# BLE_--_HM-10_--_Breakout_v0_9_4.net
KiCad netlist of a schematic drawn in EAGLE
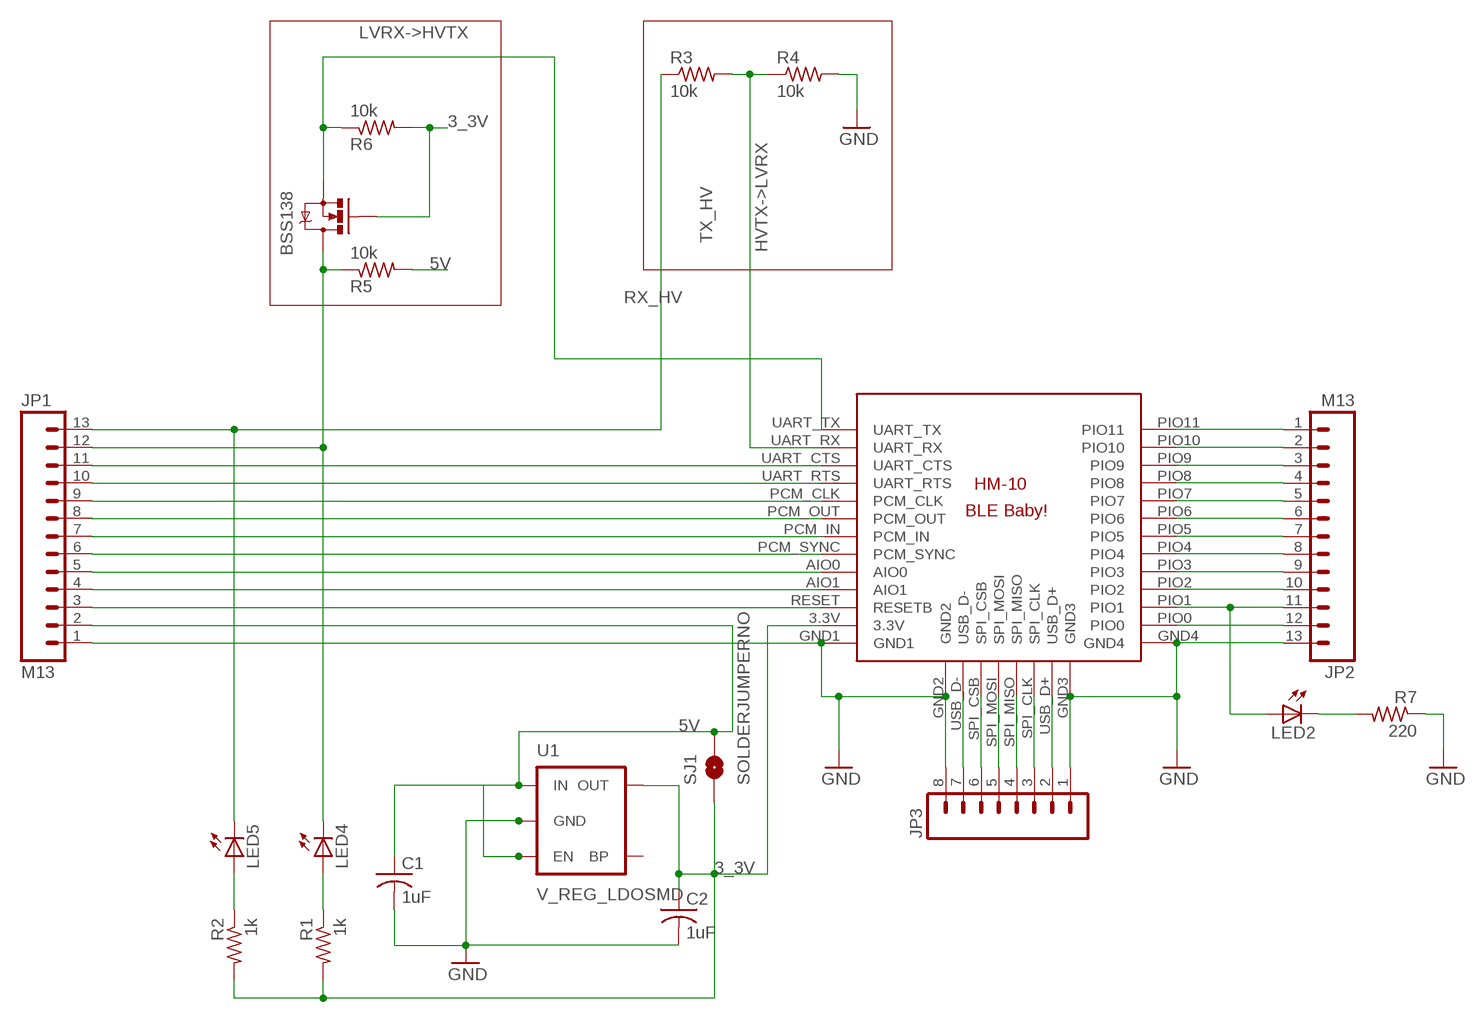
[diagram p0: schematic, sheet 1]

(export (version "E")
  (design (tool "Eeschema 10.0.6"))
  (components
    (comp (ref "BSS138")
      (value "MOSFET-NCHANNELSMD")
      (footprint "eagle-import:SOT23-3")
      (libsource (lib "eagle-import") (part "MOSFET-NCHANNELSMD"))
    )
    (comp (ref "C1")
      (value "1uF")
      (footprint "eagle-import:C0805K")
      (libsource (lib "eagle-import") (part "C-USC0805K"))
    )
    (comp (ref "C2")
      (value "1uF")
      (footprint "eagle-import:C0805K")
      (libsource (lib "eagle-import") (part "C-USC0805K"))
    )
    (comp (ref "JP1")
      (value "M13")
      (footprint "eagle-import:1X13")
      (libsource (lib "eagle-import") (part "M13"))
    )
    (comp (ref "JP2")
      (value "M13")
      (footprint "eagle-import:1X13")
      (libsource (lib "eagle-import") (part "M13"))
    )
    (comp (ref "JP3")
      (value "M081X08")
      (footprint "eagle-import:1X08")
      (libsource (lib "eagle-import") (part "M081X08"))
    )
    (comp (ref "LED2")
      (value "LED0603")
      (footprint "eagle-import:LED-0603")
      (libsource (lib "eagle-import") (part "LED0603"))
    )
    (comp (ref "LED4")
      (value "LED0603")
      (footprint "eagle-import:LED-0603")
      (libsource (lib "eagle-import") (part "LED0603"))
    )
    (comp (ref "LED5")
      (value "LED0603")
      (footprint "eagle-import:LED-0603")
      (libsource (lib "eagle-import") (part "LED0603"))
    )
    (comp (ref "R1")
      (value "1k")
      (footprint "eagle-import:M0805")
      (libsource (lib "eagle-import") (part "R-US_M0805"))
    )
    (comp (ref "R2")
      (value "1k")
      (footprint "eagle-import:M0805")
      (libsource (lib "eagle-import") (part "R-US_M0805"))
    )
    (comp (ref "R3")
      (value "10k")
      (footprint "eagle-import:M0805")
      (libsource (lib "eagle-import") (part "R-US_M0805"))
    )
    (comp (ref "R4")
      (value "10k")
      (footprint "eagle-import:M0805")
      (libsource (lib "eagle-import") (part "R-US_M0805"))
    )
    (comp (ref "R5")
      (value "10k")
      (footprint "eagle-import:M0805")
      (libsource (lib "eagle-import") (part "R-US_M0805"))
    )
    (comp (ref "R6")
      (value "10k")
      (footprint "eagle-import:M0805")
      (libsource (lib "eagle-import") (part "R-US_M0805"))
    )
    (comp (ref "R7")
      (value "220")
      (footprint "eagle-import:M0805")
      (libsource (lib "eagle-import") (part "R-US_M0805"))
    )
    (comp (ref "SJ1")
      (value "SOLDERJUMPERNO")
      (footprint "eagle-import:SJ_2S-NO")
      (libsource (lib "eagle-import") (part "SOLDERJUMPERNO"))
    )
    (comp (ref "U$1")
      (value "BLE-HM-10")
      (footprint "eagle-import:BLE-HM-10")
      (libsource (lib "eagle-import") (part "BLE-HM-10"))
    )
    (comp (ref "U1")
      (value "V_REG_LDOSMD")
      (footprint "eagle-import:SOT23-5")
      (libsource (lib "eagle-import") (part "V_REG_LDOSMD"))
    )
  )
  (nets
    (net (code "1") (name "/3_3V") (class "Default")
      (node (ref "BSS138") (pin "1") (pinfunction "G_1") (pintype "passive"))
      (node (ref "C2") (pin "1") (pinfunction "1_1") (pintype "passive"))
      (node (ref "R1") (pin "2") (pinfunction "2_2") (pintype "passive"))
      (node (ref "R2") (pin "2") (pinfunction "2_2") (pintype "passive"))
      (node (ref "R6") (pin "2") (pinfunction "2_2") (pintype "passive"))
      (node (ref "SJ1") (pin "1") (pinfunction "1_1") (pintype "passive"))
      (node (ref "U$1") (pin "3.3V") (pinfunction "3.3V_3.3V") (pintype "bidirectional"))
      (node (ref "U1") (pin "5") (pinfunction "OUT_5") (pintype "passive"))
    )
    (net (code "2") (name "/5V") (class "Default")
      (node (ref "C1") (pin "1") (pinfunction "1_1") (pintype "passive"))
      (node (ref "JP1") (pin "2") (pinfunction "2_2") (pintype "passive"))
      (node (ref "R5") (pin "2") (pinfunction "2_2") (pintype "passive"))
      (node (ref "SJ1") (pin "2") (pinfunction "2_2") (pintype "passive"))
      (node (ref "U1") (pin "1") (pinfunction "IN_1") (pintype "input"))
      (node (ref "U1") (pin "3") (pinfunction "EN_3") (pintype "input"))
    )
    (net (code "3") (name "/HVTX->LVRX") (class "Default")
      (node (ref "R3") (pin "2") (pinfunction "2_2") (pintype "passive"))
      (node (ref "R4") (pin "1") (pinfunction "1_1") (pintype "passive"))
      (node (ref "U$1") (pin "UART_RX") (pinfunction "UART_RX_UART_RX") (pintype "bidirectional"))
    )
    (net (code "4") (name "/LVRX->HVTX") (class "Default")
      (node (ref "BSS138") (pin "2") (pinfunction "S_2") (pintype "passive"))
      (node (ref "R6") (pin "1") (pinfunction "1_1") (pintype "passive"))
      (node (ref "U$1") (pin "UART_TX") (pinfunction "UART_TX_UART_TX") (pintype "bidirectional"))
    )
    (net (code "5") (name "/RX_HV") (class "Default")
      (node (ref "BSS138") (pin "3") (pinfunction "D_3") (pintype "passive"))
      (node (ref "JP1") (pin "12") (pinfunction "12_12") (pintype "passive"))
      (node (ref "LED4") (pin "C") (pinfunction "C_C") (pintype "passive"))
      (node (ref "R5") (pin "1") (pinfunction "1_1") (pintype "passive"))
    )
    (net (code "6") (name "/TX_HV") (class "Default")
      (node (ref "JP1") (pin "13") (pinfunction "13_13") (pintype "passive"))
      (node (ref "LED5") (pin "C") (pinfunction "C_C") (pintype "passive"))
      (node (ref "R3") (pin "1") (pinfunction "1_1") (pintype "passive"))
    )
    (net (code "7") (name "GND") (class "Default")
      (node (ref "C1") (pin "2") (pinfunction "2_2") (pintype "passive"))
      (node (ref "C2") (pin "2") (pinfunction "2_2") (pintype "passive"))
      (node (ref "JP1") (pin "1") (pinfunction "1_1") (pintype "passive"))
      (node (ref "JP2") (pin "13") (pinfunction "13_13") (pintype "passive"))
      (node (ref "JP3") (pin "1") (pinfunction "1_1") (pintype "passive"))
      (node (ref "JP3") (pin "8") (pinfunction "8_8") (pintype "passive"))
      (node (ref "R4") (pin "2") (pinfunction "2_2") (pintype "passive"))
      (node (ref "R7") (pin "1") (pinfunction "1_1") (pintype "passive"))
      (node (ref "U$1") (pin "GND1") (pinfunction "GND1_GND1") (pintype "bidirectional"))
      (node (ref "U$1") (pin "GND2") (pinfunction "GND2_GND2") (pintype "bidirectional"))
      (node (ref "U$1") (pin "GND3") (pinfunction "GND3_GND3") (pintype "bidirectional"))
      (node (ref "U$1") (pin "GND4") (pinfunction "GND4_GND4") (pintype "bidirectional"))
      (node (ref "U1") (pin "2") (pinfunction "GND_2") (pintype "input"))
    )
    (net (code "8") (name "Net-(JP1-Pad4)") (class "Default")
      (node (ref "JP1") (pin "4") (pinfunction "4_4") (pintype "passive"))
      (node (ref "U$1") (pin "AIO1") (pinfunction "AIO1_AIO1") (pintype "bidirectional"))
    )
    (net (code "9") (name "Net-(JP1-Pad5)") (class "Default")
      (node (ref "JP1") (pin "5") (pinfunction "5_5") (pintype "passive"))
      (node (ref "U$1") (pin "AIO0") (pinfunction "AIO0_AIO0") (pintype "bidirectional"))
    )
    (net (code "10") (name "Net-(JP1-Pad6)") (class "Default")
      (node (ref "JP1") (pin "6") (pinfunction "6_6") (pintype "passive"))
      (node (ref "U$1") (pin "PCM_SYNC") (pinfunction "PCM_SYNC_PCM_SYNC") (pintype "bidirectional"))
    )
    (net (code "11") (name "Net-(JP1-Pad7)") (class "Default")
      (node (ref "JP1") (pin "7") (pinfunction "7_7") (pintype "passive"))
      (node (ref "U$1") (pin "PCM_IN") (pinfunction "PCM_IN_PCM_IN") (pintype "bidirectional"))
    )
    (net (code "12") (name "Net-(JP1-Pad8)") (class "Default")
      (node (ref "JP1") (pin "8") (pinfunction "8_8") (pintype "passive"))
      (node (ref "U$1") (pin "PCM_OUT") (pinfunction "PCM_OUT_PCM_OUT") (pintype "bidirectional"))
    )
    (net (code "13") (name "Net-(JP1-Pad9)") (class "Default")
      (node (ref "JP1") (pin "9") (pinfunction "9_9") (pintype "passive"))
      (node (ref "U$1") (pin "PCM_CLK") (pinfunction "PCM_CLK_PCM_CLK") (pintype "bidirectional"))
    )
    (net (code "14") (name "Net-(JP1-Pad10)") (class "Default")
      (node (ref "JP1") (pin "10") (pinfunction "10_10") (pintype "passive"))
      (node (ref "U$1") (pin "UART_RTS") (pinfunction "UART_RTS_UART_RTS") (pintype "bidirectional"))
    )
    (net (code "15") (name "Net-(JP1-Pad11)") (class "Default")
      (node (ref "JP1") (pin "11") (pinfunction "11_11") (pintype "passive"))
      (node (ref "U$1") (pin "UART_CTS") (pinfunction "UART_CTS_UART_CTS") (pintype "bidirectional"))
    )
    (net (code "16") (name "Net-(JP2-Pad1)") (class "Default")
      (node (ref "JP2") (pin "1") (pinfunction "1_1") (pintype "passive"))
      (node (ref "U$1") (pin "PIO11") (pinfunction "PIO11_PIO11") (pintype "bidirectional"))
    )
    (net (code "17") (name "Net-(JP2-Pad2)") (class "Default")
      (node (ref "JP2") (pin "2") (pinfunction "2_2") (pintype "passive"))
      (node (ref "U$1") (pin "PIO10") (pinfunction "PIO10_PIO10") (pintype "bidirectional"))
    )
    (net (code "18") (name "Net-(JP2-Pad3)") (class "Default")
      (node (ref "JP2") (pin "3") (pinfunction "3_3") (pintype "passive"))
      (node (ref "U$1") (pin "PIO9") (pinfunction "PIO9_PIO9") (pintype "bidirectional"))
    )
    (net (code "19") (name "Net-(JP2-Pad4)") (class "Default")
      (node (ref "JP2") (pin "4") (pinfunction "4_4") (pintype "passive"))
      (node (ref "U$1") (pin "PIO8") (pinfunction "PIO8_PIO8") (pintype "bidirectional"))
    )
    (net (code "20") (name "Net-(JP2-Pad5)") (class "Default")
      (node (ref "JP2") (pin "5") (pinfunction "5_5") (pintype "passive"))
      (node (ref "U$1") (pin "PIO7") (pinfunction "PIO7_PIO7") (pintype "bidirectional"))
    )
    (net (code "21") (name "Net-(JP2-Pad6)") (class "Default")
      (node (ref "JP2") (pin "6") (pinfunction "6_6") (pintype "passive"))
      (node (ref "U$1") (pin "PIO6") (pinfunction "PIO6_PIO6") (pintype "bidirectional"))
    )
    (net (code "22") (name "Net-(JP2-Pad7)") (class "Default")
      (node (ref "JP2") (pin "7") (pinfunction "7_7") (pintype "passive"))
      (node (ref "U$1") (pin "PIO5") (pinfunction "PIO5_PIO5") (pintype "bidirectional"))
    )
    (net (code "23") (name "Net-(JP2-Pad8)") (class "Default")
      (node (ref "JP2") (pin "8") (pinfunction "8_8") (pintype "passive"))
      (node (ref "U$1") (pin "PIO4") (pinfunction "PIO4_PIO4") (pintype "bidirectional"))
    )
    (net (code "24") (name "Net-(JP2-Pad9)") (class "Default")
      (node (ref "JP2") (pin "9") (pinfunction "9_9") (pintype "passive"))
      (node (ref "U$1") (pin "PIO3") (pinfunction "PIO3_PIO3") (pintype "bidirectional"))
    )
    (net (code "25") (name "Net-(JP2-Pad10)") (class "Default")
      (node (ref "JP2") (pin "10") (pinfunction "10_10") (pintype "passive"))
      (node (ref "U$1") (pin "PIO2") (pinfunction "PIO2_PIO2") (pintype "bidirectional"))
    )
    (net (code "26") (name "Net-(JP2-Pad11)") (class "Default")
      (node (ref "JP2") (pin "11") (pinfunction "11_11") (pintype "passive"))
      (node (ref "LED2") (pin "A") (pinfunction "A_A") (pintype "passive"))
      (node (ref "U$1") (pin "PIO1") (pinfunction "PIO1_PIO1") (pintype "bidirectional"))
    )
    (net (code "27") (name "Net-(JP2-Pad12)") (class "Default")
      (node (ref "JP2") (pin "12") (pinfunction "12_12") (pintype "passive"))
      (node (ref "U$1") (pin "PIO0") (pinfunction "PIO0_PIO0") (pintype "bidirectional"))
    )
    (net (code "28") (name "Net-(JP3-Pad2)") (class "Default")
      (node (ref "JP3") (pin "2") (pinfunction "2_2") (pintype "passive"))
      (node (ref "U$1") (pin "USB_D+") (pinfunction "USB_D+_USB_D+") (pintype "bidirectional"))
    )
    (net (code "29") (name "Net-(JP3-Pad3)") (class "Default")
      (node (ref "JP3") (pin "3") (pinfunction "3_3") (pintype "passive"))
      (node (ref "U$1") (pin "SPI_CLK") (pinfunction "SPI_CLK_SPI_CLK") (pintype "bidirectional"))
    )
    (net (code "30") (name "Net-(JP3-Pad4)") (class "Default")
      (node (ref "JP3") (pin "4") (pinfunction "4_4") (pintype "passive"))
      (node (ref "U$1") (pin "SPI_MISO") (pinfunction "SPI_MISO_SPI_MISO") (pintype "bidirectional"))
    )
    (net (code "31") (name "Net-(JP3-Pad5)") (class "Default")
      (node (ref "JP3") (pin "5") (pinfunction "5_5") (pintype "passive"))
      (node (ref "U$1") (pin "SPI_MOSI") (pinfunction "SPI_MOSI_SPI_MOSI") (pintype "bidirectional"))
    )
    (net (code "32") (name "Net-(JP3-Pad6)") (class "Default")
      (node (ref "JP3") (pin "6") (pinfunction "6_6") (pintype "passive"))
      (node (ref "U$1") (pin "SPI_CSB") (pinfunction "SPI_CSB_SPI_CSB") (pintype "bidirectional"))
    )
    (net (code "33") (name "Net-(JP3-Pad7)") (class "Default")
      (node (ref "JP3") (pin "7") (pinfunction "7_7") (pintype "passive"))
      (node (ref "U$1") (pin "USB_D-") (pinfunction "USB_D-_USB_D-") (pintype "bidirectional"))
    )
    (net (code "34") (name "Net-(LED2-PadC)") (class "Default")
      (node (ref "LED2") (pin "C") (pinfunction "C_C") (pintype "passive"))
      (node (ref "R7") (pin "2") (pinfunction "2_2") (pintype "passive"))
    )
    (net (code "35") (name "Net-(LED4-PadA)") (class "Default")
      (node (ref "LED4") (pin "A") (pinfunction "A_A") (pintype "passive"))
      (node (ref "R1") (pin "1") (pinfunction "1_1") (pintype "passive"))
    )
    (net (code "36") (name "Net-(LED5-PadA)") (class "Default")
      (node (ref "LED5") (pin "A") (pinfunction "A_A") (pintype "passive"))
      (node (ref "R2") (pin "1") (pinfunction "1_1") (pintype "passive"))
    )
    (net (code "37") (name "Net-(U$1-RESETB)") (class "Default")
      (node (ref "JP1") (pin "3") (pinfunction "3_3") (pintype "passive"))
      (node (ref "U$1") (pin "RESET") (pinfunction "RESETB_RESET") (pintype "bidirectional"))
    )
    (net (code "38") (name "unconnected-(U1-BP-Pad4)") (class "Default")
      (node (ref "U1") (pin "4") (pinfunction "BP_4") (pintype "input"))
    )
  )
)
